# G221X.net
KiCad netlist of a schematic drawn in EAGLE
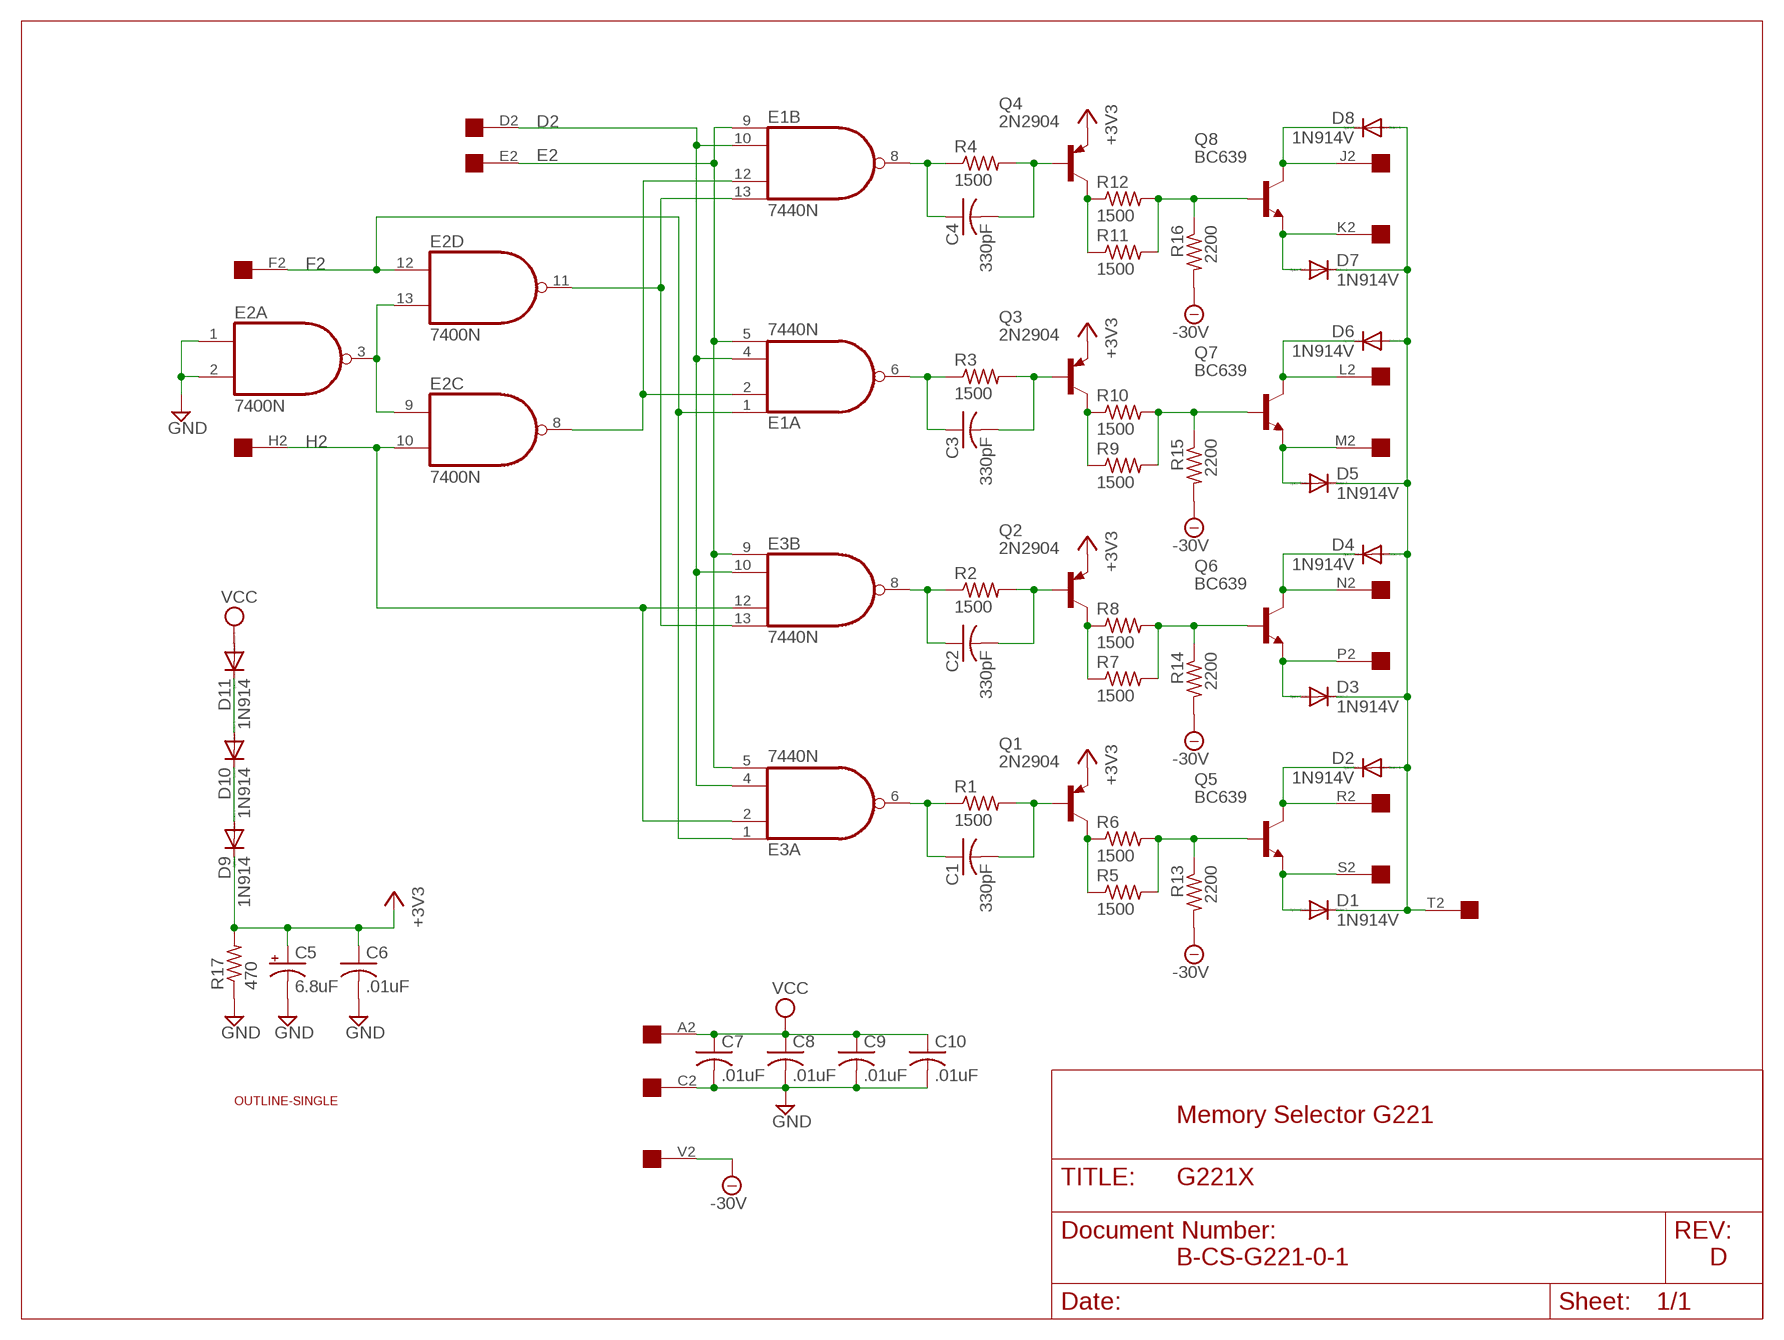
[diagram p0: schematic, sheet 1]

(export (version "E")
  (design (tool "Eeschema 10.0.6"))
  (components
    (comp (ref "C1")
      (value "330pF")
      (footprint "eagle-import:C050-025X075")
      (libsource (lib "eagle-import") (part "C-US050-025X075"))
    )
    (comp (ref "C2")
      (value "330pF")
      (footprint "eagle-import:C050-025X075")
      (libsource (lib "eagle-import") (part "C-US050-025X075"))
    )
    (comp (ref "C3")
      (value "330pF")
      (footprint "eagle-import:C050-025X075")
      (libsource (lib "eagle-import") (part "C-US050-025X075"))
    )
    (comp (ref "C4")
      (value "330pF")
      (footprint "eagle-import:C050-025X075")
      (libsource (lib "eagle-import") (part "C-US050-025X075"))
    )
    (comp (ref "C5")
      (value "6.8uF")
      (footprint "eagle-import:E12-8")
      (libsource (lib "eagle-import") (part "CPOL-USE20-8AXIAL"))
    )
    (comp (ref "C6")
      (value ".01uF")
      (footprint "eagle-import:C050-025X075")
      (libsource (lib "eagle-import") (part "C-US050-025X075"))
    )
    (comp (ref "C7")
      (value ".01uF")
      (footprint "eagle-import:C050-025X075")
      (libsource (lib "eagle-import") (part "C-US050-025X075"))
    )
    (comp (ref "C8")
      (value ".01uF")
      (footprint "eagle-import:C050-025X075")
      (libsource (lib "eagle-import") (part "C-US050-025X075"))
    )
    (comp (ref "C9")
      (value ".01uF")
      (footprint "eagle-import:C050-025X075")
      (libsource (lib "eagle-import") (part "C-US050-025X075"))
    )
    (comp (ref "C10")
      (value ".01uF")
      (footprint "eagle-import:C050-025X075")
      (libsource (lib "eagle-import") (part "C-US050-025X075"))
    )
    (comp (ref "D1")
      (value "1N914V")
      (footprint "eagle-import:DO35-10")
      (libsource (lib "eagle-import") (part "1N4148DO35-10"))
    )
    (comp (ref "D2")
      (value "1N914V")
      (footprint "eagle-import:DO35-10")
      (libsource (lib "eagle-import") (part "1N4148DO35-10"))
    )
    (comp (ref "D3")
      (value "1N914V")
      (footprint "eagle-import:DO35-10")
      (libsource (lib "eagle-import") (part "1N4148DO35-10"))
    )
    (comp (ref "D4")
      (value "1N914V")
      (footprint "eagle-import:DO35-10")
      (libsource (lib "eagle-import") (part "1N4148DO35-10"))
    )
    (comp (ref "D5")
      (value "1N914V")
      (footprint "eagle-import:DO35-10")
      (libsource (lib "eagle-import") (part "1N4148DO35-10"))
    )
    (comp (ref "D6")
      (value "1N914V")
      (footprint "eagle-import:DO35-10")
      (libsource (lib "eagle-import") (part "1N4148DO35-10"))
    )
    (comp (ref "D7")
      (value "1N914V")
      (footprint "eagle-import:DO35-10")
      (libsource (lib "eagle-import") (part "1N4148DO35-10"))
    )
    (comp (ref "D8")
      (value "1N914V")
      (footprint "eagle-import:DO35-10")
      (libsource (lib "eagle-import") (part "1N4148DO35-10"))
    )
    (comp (ref "D9")
      (value "1N914")
      (footprint "eagle-import:DO35-10")
      (libsource (lib "eagle-import") (part "1N4148DO35-10"))
    )
    (comp (ref "D10")
      (value "1N914")
      (footprint "eagle-import:DO35-10")
      (libsource (lib "eagle-import") (part "1N4148DO35-10"))
    )
    (comp (ref "D11")
      (value "1N914")
      (footprint "eagle-import:DO35-10")
      (libsource (lib "eagle-import") (part "1N4148DO35-10"))
    )
    (comp (ref "E1")
      (value "7440N")
      (footprint "eagle-import:DIL14")
      (libsource (lib "eagle-import") (part "7420NS"))
    )
    (comp (ref "E2")
      (value "7400N")
      (footprint "eagle-import:DIL14")
      (libsource (lib "eagle-import") (part "7400N"))
    )
    (comp (ref "E3")
      (value "7440N")
      (footprint "eagle-import:DIL14")
      (libsource (lib "eagle-import") (part "7420NS"))
    )
    (comp (ref "Q1")
      (value "2N2904")
      (footprint "eagle-import:TO39")
      (libsource (lib "eagle-import") (part "2N2904"))
    )
    (comp (ref "Q2")
      (value "2N2904")
      (footprint "eagle-import:TO39")
      (libsource (lib "eagle-import") (part "2N2904"))
    )
    (comp (ref "Q3")
      (value "2N2904")
      (footprint "eagle-import:TO39")
      (libsource (lib "eagle-import") (part "2N2904"))
    )
    (comp (ref "Q4")
      (value "2N2904")
      (footprint "eagle-import:TO39")
      (libsource (lib "eagle-import") (part "2N2904"))
    )
    (comp (ref "Q5")
      (value "BC639")
      (footprint "eagle-import:TO39")
      (libsource (lib "eagle-import") (part "-NPN-TO39-EBC2N1613"))
    )
    (comp (ref "Q6")
      (value "BC639")
      (footprint "eagle-import:TO39")
      (libsource (lib "eagle-import") (part "-NPN-TO39-EBC2N1613"))
    )
    (comp (ref "Q7")
      (value "BC639")
      (footprint "eagle-import:TO39")
      (libsource (lib "eagle-import") (part "-NPN-TO39-EBC2N1613"))
    )
    (comp (ref "Q8")
      (value "BC639")
      (footprint "eagle-import:TO39")
      (libsource (lib "eagle-import") (part "-NPN-TO39-EBC2N1613"))
    )
    (comp (ref "R1")
      (value "1500")
      (footprint "eagle-import:0207_10")
      (libsource (lib "eagle-import") (part "R-US_0207/10"))
    )
    (comp (ref "R2")
      (value "1500")
      (footprint "eagle-import:0207_10")
      (libsource (lib "eagle-import") (part "R-US_0207/10"))
    )
    (comp (ref "R3")
      (value "1500")
      (footprint "eagle-import:0207_10")
      (libsource (lib "eagle-import") (part "R-US_0207/10"))
    )
    (comp (ref "R4")
      (value "1500")
      (footprint "eagle-import:0207_10")
      (libsource (lib "eagle-import") (part "R-US_0207/10"))
    )
    (comp (ref "R5")
      (value "1500")
      (footprint "eagle-import:0207_10")
      (libsource (lib "eagle-import") (part "R-US_0207/10"))
    )
    (comp (ref "R6")
      (value "1500")
      (footprint "eagle-import:0207_10")
      (libsource (lib "eagle-import") (part "R-US_0207/10"))
    )
    (comp (ref "R7")
      (value "1500")
      (footprint "eagle-import:0207_10")
      (libsource (lib "eagle-import") (part "R-US_0207/10"))
    )
    (comp (ref "R8")
      (value "1500")
      (footprint "eagle-import:0207_10")
      (libsource (lib "eagle-import") (part "R-US_0207/10"))
    )
    (comp (ref "R9")
      (value "1500")
      (footprint "eagle-import:0207_10")
      (libsource (lib "eagle-import") (part "R-US_0207/10"))
    )
    (comp (ref "R10")
      (value "1500")
      (footprint "eagle-import:0207_10")
      (libsource (lib "eagle-import") (part "R-US_0207/10"))
    )
    (comp (ref "R11")
      (value "1500")
      (footprint "eagle-import:0207_10")
      (libsource (lib "eagle-import") (part "R-US_0207/10"))
    )
    (comp (ref "R12")
      (value "1500")
      (footprint "eagle-import:0207_10")
      (libsource (lib "eagle-import") (part "R-US_0207/10"))
    )
    (comp (ref "R13")
      (value "2200")
      (footprint "eagle-import:0207_10")
      (libsource (lib "eagle-import") (part "R-US_0207/10"))
    )
    (comp (ref "R14")
      (value "2200")
      (footprint "eagle-import:0207_10")
      (libsource (lib "eagle-import") (part "R-US_0207/10"))
    )
    (comp (ref "R15")
      (value "2200")
      (footprint "eagle-import:0207_10")
      (libsource (lib "eagle-import") (part "R-US_0207/10"))
    )
    (comp (ref "R16")
      (value "2200")
      (footprint "eagle-import:0207_10")
      (libsource (lib "eagle-import") (part "R-US_0207/10"))
    )
    (comp (ref "R17")
      (value "470")
      (footprint "eagle-import:0207_10")
      (libsource (lib "eagle-import") (part "R-US_0207/10"))
    )
    (comp (ref "U$1")
      (value "EDGE-1")
      (footprint "eagle-import:EDGE-CON1")
      (libsource (lib "eagle-import") (part "EDGE-1"))
    )
    (comp (ref "U$7")
      (value "OUTLINE-SINGLE")
      (footprint "eagle-import:SINGLE")
      (libsource (lib "eagle-import") (part "OUTLINE-SINGLE"))
    )
  )
  (nets
    (net (code "1") (name "+3V3") (class "Default")
      (node (ref "C5") (pin "+") (pinfunction "+_+") (pintype "passive"))
      (node (ref "C6") (pin "1") (pinfunction "1_1") (pintype "passive"))
      (node (ref "D9") (pin "C") (pinfunction "C_C") (pintype "passive"))
      (node (ref "Q1") (pin "1") (pinfunction "E_1") (pintype "passive"))
      (node (ref "Q2") (pin "1") (pinfunction "E_1") (pintype "passive"))
      (node (ref "Q3") (pin "1") (pinfunction "E_1") (pintype "passive"))
      (node (ref "Q4") (pin "1") (pinfunction "E_1") (pintype "passive"))
      (node (ref "R17") (pin "2") (pinfunction "2_2") (pintype "passive"))
    )
    (net (code "2") (name "-30V") (class "Default")
      (node (ref "R13") (pin "2") (pinfunction "2_2") (pintype "passive"))
      (node (ref "R14") (pin "2") (pinfunction "2_2") (pintype "passive"))
      (node (ref "R15") (pin "2") (pinfunction "2_2") (pintype "passive"))
      (node (ref "R16") (pin "2") (pinfunction "2_2") (pintype "passive"))
      (node (ref "U$1") (pin "V2") (pinfunction "1_V2") (pintype "bidirectional"))
    )
    (net (code "3") (name "/D2") (class "Default")
      (node (ref "E1") (pin "10") (pinfunction "I1_10") (pintype "input"))
      (node (ref "E1") (pin "4") (pinfunction "I2_4") (pintype "input"))
      (node (ref "E3") (pin "10") (pinfunction "I1_10") (pintype "input"))
      (node (ref "E3") (pin "4") (pinfunction "I2_4") (pintype "input"))
      (node (ref "U$1") (pin "D2") (pinfunction "1_D2") (pintype "bidirectional"))
    )
    (net (code "4") (name "/E2") (class "Default")
      (node (ref "E1") (pin "5") (pinfunction "I3_5") (pintype "input"))
      (node (ref "E1") (pin "9") (pinfunction "I0_9") (pintype "input"))
      (node (ref "E3") (pin "5") (pinfunction "I3_5") (pintype "input"))
      (node (ref "E3") (pin "9") (pinfunction "I0_9") (pintype "input"))
      (node (ref "U$1") (pin "E2") (pinfunction "1_E2") (pintype "bidirectional"))
    )
    (net (code "5") (name "/F2") (class "Default")
      (node (ref "E1") (pin "1") (pinfunction "I0_1") (pintype "input"))
      (node (ref "E2") (pin "12") (pinfunction "I0_12") (pintype "input"))
      (node (ref "E3") (pin "1") (pinfunction "I0_1") (pintype "input"))
      (node (ref "U$1") (pin "F2") (pinfunction "1_F2") (pintype "bidirectional"))
    )
    (net (code "6") (name "/H2") (class "Default")
      (node (ref "E2") (pin "10") (pinfunction "I1_10") (pintype "input"))
      (node (ref "E3") (pin "12") (pinfunction "I2_12") (pintype "input"))
      (node (ref "E3") (pin "2") (pinfunction "I1_2") (pintype "input"))
      (node (ref "U$1") (pin "H2") (pinfunction "1_H2") (pintype "bidirectional"))
    )
    (net (code "7") (name "GND") (class "Default")
      (node (ref "C10") (pin "2") (pinfunction "2_2") (pintype "passive"))
      (node (ref "C5") (pin "-") (pinfunction "-_-") (pintype "passive"))
      (node (ref "C6") (pin "2") (pinfunction "2_2") (pintype "passive"))
      (node (ref "C7") (pin "2") (pinfunction "2_2") (pintype "passive"))
      (node (ref "C8") (pin "2") (pinfunction "2_2") (pintype "passive"))
      (node (ref "C9") (pin "2") (pinfunction "2_2") (pintype "passive"))
      (node (ref "E2") (pin "1") (pinfunction "I0_1") (pintype "input"))
      (node (ref "E2") (pin "2") (pinfunction "I1_2") (pintype "input"))
      (node (ref "R17") (pin "1") (pinfunction "1_1") (pintype "passive"))
      (node (ref "U$1") (pin "C2") (pinfunction "1_C2") (pintype "bidirectional"))
    )
    (net (code "8") (name "Net-(D10-PadA)") (class "Default")
      (node (ref "D10") (pin "A") (pinfunction "A_A") (pintype "passive"))
      (node (ref "D11") (pin "C") (pinfunction "C_C") (pintype "passive"))
    )
    (net (code "9") (name "Net-(D10-PadC)") (class "Default")
      (node (ref "D10") (pin "C") (pinfunction "C_C") (pintype "passive"))
      (node (ref "D9") (pin "A") (pinfunction "A_A") (pintype "passive"))
    )
    (net (code "10") (name "Net-(E1A-I1)") (class "Default")
      (node (ref "E1") (pin "12") (pinfunction "I2_12") (pintype "input"))
      (node (ref "E1") (pin "2") (pinfunction "I1_2") (pintype "input"))
      (node (ref "E2") (pin "8") (pinfunction "O_8") (pintype "output"))
    )
    (net (code "11") (name "Net-(E1A-O)") (class "Default")
      (node (ref "C3") (pin "1") (pinfunction "1_1") (pintype "passive"))
      (node (ref "E1") (pin "6") (pinfunction "O_6") (pintype "output"))
      (node (ref "R3") (pin "1") (pinfunction "1_1") (pintype "passive"))
    )
    (net (code "12") (name "Net-(E1B-I3)") (class "Default")
      (node (ref "E1") (pin "13") (pinfunction "I3_13") (pintype "input"))
      (node (ref "E2") (pin "11") (pinfunction "O_11") (pintype "output"))
      (node (ref "E3") (pin "13") (pinfunction "I3_13") (pintype "input"))
    )
    (net (code "13") (name "Net-(E1B-O)") (class "Default")
      (node (ref "C4") (pin "1") (pinfunction "1_1") (pintype "passive"))
      (node (ref "E1") (pin "8") (pinfunction "O_8") (pintype "output"))
      (node (ref "R4") (pin "1") (pinfunction "1_1") (pintype "passive"))
    )
    (net (code "14") (name "Net-(E2A-O)") (class "Default")
      (node (ref "E2") (pin "13") (pinfunction "I1_13") (pintype "input"))
      (node (ref "E2") (pin "3") (pinfunction "O_3") (pintype "output"))
      (node (ref "E2") (pin "9") (pinfunction "I0_9") (pintype "input"))
    )
    (net (code "15") (name "Net-(E3A-O)") (class "Default")
      (node (ref "C1") (pin "1") (pinfunction "1_1") (pintype "passive"))
      (node (ref "E3") (pin "6") (pinfunction "O_6") (pintype "output"))
      (node (ref "R1") (pin "1") (pinfunction "1_1") (pintype "passive"))
    )
    (net (code "16") (name "Net-(E3B-O)") (class "Default")
      (node (ref "C2") (pin "1") (pinfunction "1_1") (pintype "passive"))
      (node (ref "E3") (pin "8") (pinfunction "O_8") (pintype "output"))
      (node (ref "R2") (pin "1") (pinfunction "1_1") (pintype "passive"))
    )
    (net (code "17") (name "Net-(Q1-B)") (class "Default")
      (node (ref "C1") (pin "2") (pinfunction "2_2") (pintype "passive"))
      (node (ref "Q1") (pin "2") (pinfunction "B_2") (pintype "passive"))
      (node (ref "R1") (pin "2") (pinfunction "2_2") (pintype "passive"))
    )
    (net (code "18") (name "Net-(Q1-C)") (class "Default")
      (node (ref "Q1") (pin "3") (pinfunction "C_3") (pintype "passive"))
      (node (ref "R5") (pin "1") (pinfunction "1_1") (pintype "passive"))
      (node (ref "R6") (pin "1") (pinfunction "1_1") (pintype "passive"))
    )
    (net (code "19") (name "Net-(Q2-B)") (class "Default")
      (node (ref "C2") (pin "2") (pinfunction "2_2") (pintype "passive"))
      (node (ref "Q2") (pin "2") (pinfunction "B_2") (pintype "passive"))
      (node (ref "R2") (pin "2") (pinfunction "2_2") (pintype "passive"))
    )
    (net (code "20") (name "Net-(Q2-C)") (class "Default")
      (node (ref "Q2") (pin "3") (pinfunction "C_3") (pintype "passive"))
      (node (ref "R7") (pin "1") (pinfunction "1_1") (pintype "passive"))
      (node (ref "R8") (pin "1") (pinfunction "1_1") (pintype "passive"))
    )
    (net (code "21") (name "Net-(Q3-B)") (class "Default")
      (node (ref "C3") (pin "2") (pinfunction "2_2") (pintype "passive"))
      (node (ref "Q3") (pin "2") (pinfunction "B_2") (pintype "passive"))
      (node (ref "R3") (pin "2") (pinfunction "2_2") (pintype "passive"))
    )
    (net (code "22") (name "Net-(Q3-C)") (class "Default")
      (node (ref "Q3") (pin "3") (pinfunction "C_3") (pintype "passive"))
      (node (ref "R10") (pin "1") (pinfunction "1_1") (pintype "passive"))
      (node (ref "R9") (pin "1") (pinfunction "1_1") (pintype "passive"))
    )
    (net (code "23") (name "Net-(Q4-B)") (class "Default")
      (node (ref "C4") (pin "2") (pinfunction "2_2") (pintype "passive"))
      (node (ref "Q4") (pin "2") (pinfunction "B_2") (pintype "passive"))
      (node (ref "R4") (pin "2") (pinfunction "2_2") (pintype "passive"))
    )
    (net (code "24") (name "Net-(Q4-C)") (class "Default")
      (node (ref "Q4") (pin "3") (pinfunction "C_3") (pintype "passive"))
      (node (ref "R11") (pin "1") (pinfunction "1_1") (pintype "passive"))
      (node (ref "R12") (pin "1") (pinfunction "1_1") (pintype "passive"))
    )
    (net (code "25") (name "Net-(Q5-B)") (class "Default")
      (node (ref "Q5") (pin "2") (pinfunction "B_2") (pintype "passive"))
      (node (ref "R13") (pin "1") (pinfunction "1_1") (pintype "passive"))
      (node (ref "R5") (pin "2") (pinfunction "2_2") (pintype "passive"))
      (node (ref "R6") (pin "2") (pinfunction "2_2") (pintype "passive"))
    )
    (net (code "26") (name "Net-(Q5-C)") (class "Default")
      (node (ref "D2") (pin "C") (pinfunction "C_C") (pintype "passive"))
      (node (ref "Q5") (pin "3") (pinfunction "C_3") (pintype "passive"))
      (node (ref "U$1") (pin "R2") (pinfunction "1_R2") (pintype "bidirectional"))
    )
    (net (code "27") (name "Net-(Q5-E)") (class "Default")
      (node (ref "D1") (pin "A") (pinfunction "A_A") (pintype "passive"))
      (node (ref "Q5") (pin "1") (pinfunction "E_1") (pintype "passive"))
      (node (ref "U$1") (pin "S2") (pinfunction "1_S2") (pintype "bidirectional"))
    )
    (net (code "28") (name "Net-(Q6-B)") (class "Default")
      (node (ref "Q6") (pin "2") (pinfunction "B_2") (pintype "passive"))
      (node (ref "R14") (pin "1") (pinfunction "1_1") (pintype "passive"))
      (node (ref "R7") (pin "2") (pinfunction "2_2") (pintype "passive"))
      (node (ref "R8") (pin "2") (pinfunction "2_2") (pintype "passive"))
    )
    (net (code "29") (name "Net-(Q6-C)") (class "Default")
      (node (ref "D4") (pin "C") (pinfunction "C_C") (pintype "passive"))
      (node (ref "Q6") (pin "3") (pinfunction "C_3") (pintype "passive"))
      (node (ref "U$1") (pin "N2") (pinfunction "1_N2") (pintype "bidirectional"))
    )
    (net (code "30") (name "Net-(Q6-E)") (class "Default")
      (node (ref "D3") (pin "A") (pinfunction "A_A") (pintype "passive"))
      (node (ref "Q6") (pin "1") (pinfunction "E_1") (pintype "passive"))
      (node (ref "U$1") (pin "P2") (pinfunction "1_P2") (pintype "bidirectional"))
    )
    (net (code "31") (name "Net-(Q7-B)") (class "Default")
      (node (ref "Q7") (pin "2") (pinfunction "B_2") (pintype "passive"))
      (node (ref "R10") (pin "2") (pinfunction "2_2") (pintype "passive"))
      (node (ref "R15") (pin "1") (pinfunction "1_1") (pintype "passive"))
      (node (ref "R9") (pin "2") (pinfunction "2_2") (pintype "passive"))
    )
    (net (code "32") (name "Net-(Q7-C)") (class "Default")
      (node (ref "D6") (pin "C") (pinfunction "C_C") (pintype "passive"))
      (node (ref "Q7") (pin "3") (pinfunction "C_3") (pintype "passive"))
      (node (ref "U$1") (pin "L2") (pinfunction "1_L2") (pintype "bidirectional"))
    )
    (net (code "33") (name "Net-(Q7-E)") (class "Default")
      (node (ref "D5") (pin "A") (pinfunction "A_A") (pintype "passive"))
      (node (ref "Q7") (pin "1") (pinfunction "E_1") (pintype "passive"))
      (node (ref "U$1") (pin "M2") (pinfunction "1_M2") (pintype "bidirectional"))
    )
    (net (code "34") (name "Net-(Q8-B)") (class "Default")
      (node (ref "Q8") (pin "2") (pinfunction "B_2") (pintype "passive"))
      (node (ref "R11") (pin "2") (pinfunction "2_2") (pintype "passive"))
      (node (ref "R12") (pin "2") (pinfunction "2_2") (pintype "passive"))
      (node (ref "R16") (pin "1") (pinfunction "1_1") (pintype "passive"))
    )
    (net (code "35") (name "Net-(Q8-C)") (class "Default")
      (node (ref "D8") (pin "C") (pinfunction "C_C") (pintype "passive"))
      (node (ref "Q8") (pin "3") (pinfunction "C_3") (pintype "passive"))
      (node (ref "U$1") (pin "J2") (pinfunction "1_J2") (pintype "bidirectional"))
    )
    (net (code "36") (name "Net-(Q8-E)") (class "Default")
      (node (ref "D7") (pin "A") (pinfunction "A_A") (pintype "passive"))
      (node (ref "Q8") (pin "1") (pinfunction "E_1") (pintype "passive"))
      (node (ref "U$1") (pin "K2") (pinfunction "1_K2") (pintype "bidirectional"))
    )
    (net (code "37") (name "Net-(U$1P-1)") (class "Default")
      (node (ref "D1") (pin "C") (pinfunction "C_C") (pintype "passive"))
      (node (ref "D2") (pin "A") (pinfunction "A_A") (pintype "passive"))
      (node (ref "D3") (pin "C") (pinfunction "C_C") (pintype "passive"))
      (node (ref "D4") (pin "A") (pinfunction "A_A") (pintype "passive"))
      (node (ref "D5") (pin "C") (pinfunction "C_C") (pintype "passive"))
      (node (ref "D6") (pin "A") (pinfunction "A_A") (pintype "passive"))
      (node (ref "D7") (pin "C") (pinfunction "C_C") (pintype "passive"))
      (node (ref "D8") (pin "A") (pinfunction "A_A") (pintype "passive"))
      (node (ref "U$1") (pin "T2") (pinfunction "1_T2") (pintype "bidirectional"))
    )
    (net (code "38") (name "VCC") (class "Default")
      (node (ref "C10") (pin "1") (pinfunction "1_1") (pintype "passive"))
      (node (ref "C7") (pin "1") (pinfunction "1_1") (pintype "passive"))
      (node (ref "C8") (pin "1") (pinfunction "1_1") (pintype "passive"))
      (node (ref "C9") (pin "1") (pinfunction "1_1") (pintype "passive"))
      (node (ref "D11") (pin "A") (pinfunction "A_A") (pintype "passive"))
      (node (ref "U$1") (pin "A2") (pinfunction "1_A2") (pintype "bidirectional"))
    )
  )
)
